# 02_VI-adc.net
KiCad netlist of a schematic drawn in Altium Designer
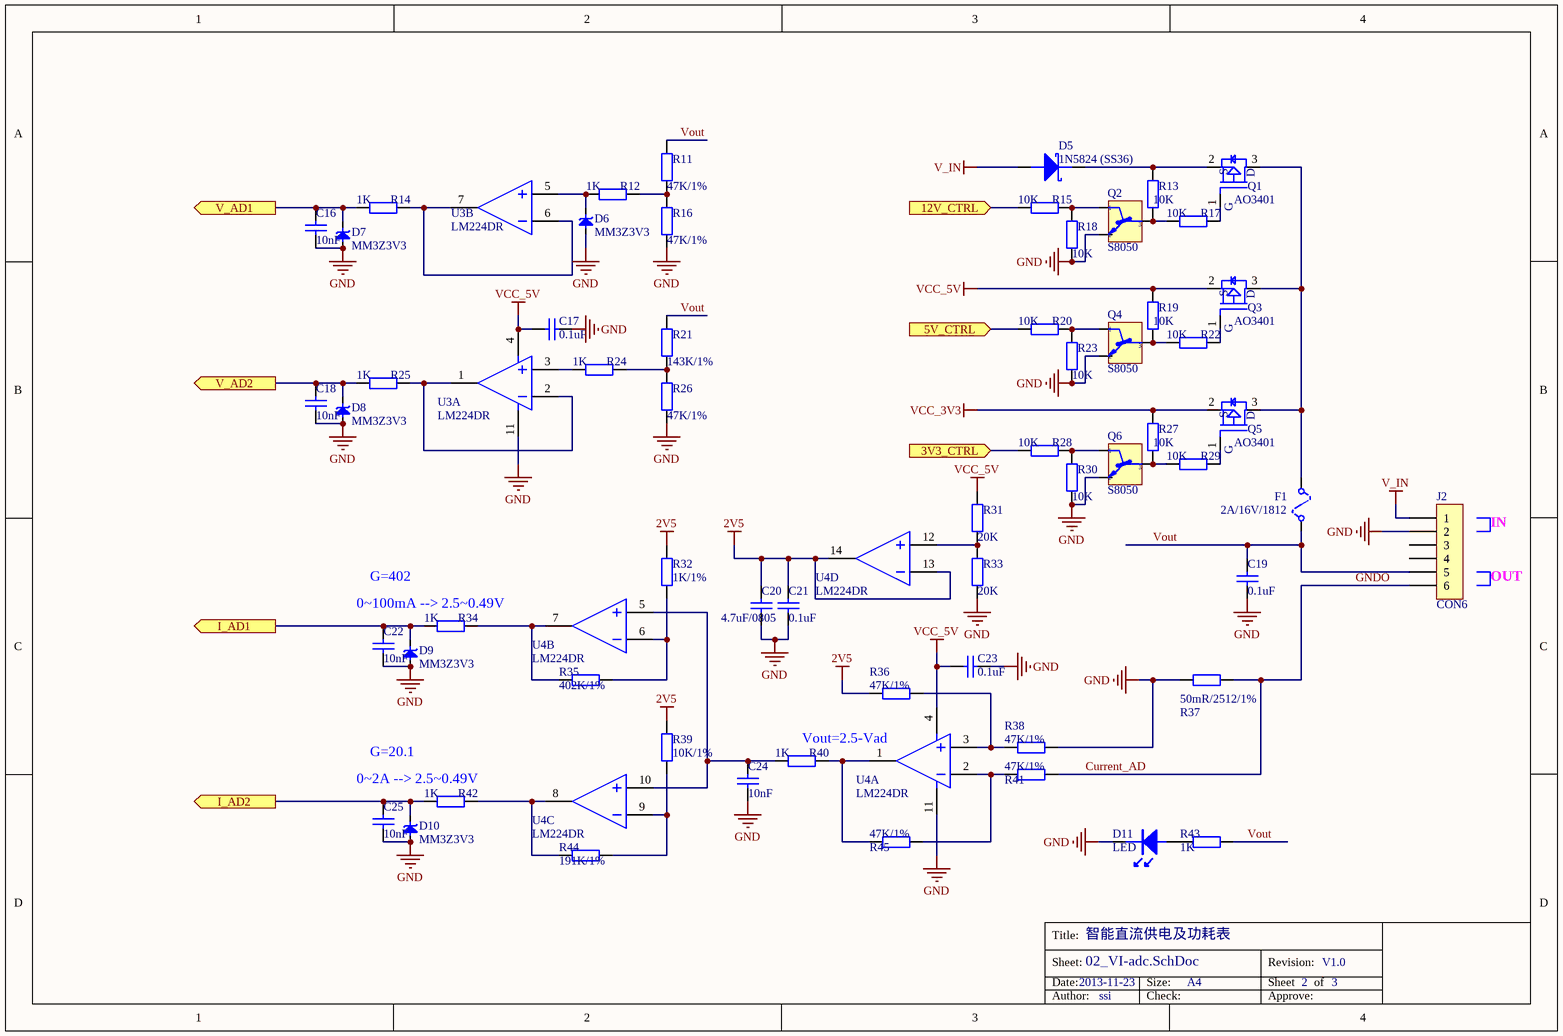
[diagram p0: 02_VI-adc.SchDoc]

(export (version "E")
  (design (tool "Eeschema 10.0.6"))
  (components
    (comp (ref "C16")
      (value "10nF")
      (footprint "0603C")
      (description "Capacitor")
      (fields (field (name "PUBLISHER") "Altium Limited"))
      (libsource (lib "SSD-Schlib1") (part "Cap"))
    )
    (comp (ref "C17")
      (value "0.1uF")
      (footprint "0603C")
      (description "Capacitor")
      (fields (field (name "PUBLISHER") "Altium Limited"))
      (libsource (lib "SSD-Schlib1") (part "Cap"))
    )
    (comp (ref "C18")
      (value "10nF")
      (footprint "0603C")
      (description "Capacitor")
      (fields (field (name "PUBLISHER") "Altium Limited"))
      (libsource (lib "SSD-Schlib1") (part "Cap"))
    )
    (comp (ref "C19")
      (value "0.1uF")
      (footprint "0603C")
      (description "Capacitor")
      (fields (field (name "PUBLISHER") "Altium Limited"))
      (libsource (lib "SSD-Schlib1") (part "Cap"))
    )
    (comp (ref "C20")
      (value "4.7uF/0805")
      (footprint "0805")
      (description "Capacitor")
      (fields (field (name "PUBLISHER") "Altium Limited"))
      (libsource (lib "SSD-Schlib1") (part "Cap"))
    )
    (comp (ref "C21")
      (value "0.1uF")
      (footprint "0603C")
      (description "Capacitor")
      (fields (field (name "PUBLISHER") "Altium Limited"))
      (libsource (lib "SSD-Schlib1") (part "Cap"))
    )
    (comp (ref "C22")
      (value "10nF")
      (footprint "0603C")
      (description "Capacitor")
      (fields (field (name "PUBLISHER") "Altium Limited"))
      (libsource (lib "SSD-Schlib1") (part "Cap"))
    )
    (comp (ref "C23")
      (value "0.1uF")
      (footprint "0603C")
      (description "Capacitor")
      (fields (field (name "PUBLISHER") "Altium Limited"))
      (libsource (lib "SSD-Schlib1") (part "Cap"))
    )
    (comp (ref "C24")
      (value "10nF")
      (footprint "0603C")
      (description "Capacitor")
      (fields (field (name "PUBLISHER") "Altium Limited"))
      (libsource (lib "SSD-Schlib1") (part "Cap"))
    )
    (comp (ref "C25")
      (value "10nF")
      (footprint "0603C")
      (description "Capacitor")
      (fields (field (name "PUBLISHER") "Altium Limited"))
      (libsource (lib "SSD-Schlib1") (part "Cap"))
    )
    (comp (ref "D5")
      (value "1N5824 (SS36)")
      (footprint "SMA/DO-214AC")
      (description "Schottky Diode")
      (libsource (lib "SSD-Schlib1") (part "DIODE_1N582x"))
    )
    (comp (ref "D6")
      (value "MM3Z3V3")
      (footprint "SOD-323")
      (description "Zener Diode")
      (fields (field (name "PUBLISHER") "Altium Limited"))
      (libsource (lib "SSD-Schlib1") (part "DIODE_MM3Zxx"))
    )
    (comp (ref "D7")
      (value "MM3Z3V3")
      (footprint "SOD-323")
      (description "Zener Diode")
      (fields (field (name "PUBLISHER") "Altium Limited"))
      (libsource (lib "SSD-Schlib1") (part "DIODE_MM3Zxx"))
    )
    (comp (ref "D8")
      (value "MM3Z3V3")
      (footprint "SOD-323")
      (description "Zener Diode")
      (fields (field (name "PUBLISHER") "Altium Limited"))
      (libsource (lib "SSD-Schlib1") (part "DIODE_MM3Zxx"))
    )
    (comp (ref "D9")
      (value "MM3Z3V3")
      (footprint "SOD-323")
      (description "Zener Diode")
      (fields (field (name "PUBLISHER") "Altium Limited"))
      (libsource (lib "SSD-Schlib1") (part "DIODE_MM3Zxx"))
    )
    (comp (ref "D10")
      (value "MM3Z3V3")
      (footprint "SOD-323")
      (description "Zener Diode")
      (fields (field (name "PUBLISHER") "Altium Limited"))
      (libsource (lib "SSD-Schlib1") (part "DIODE_MM3Zxx"))
    )
    (comp (ref "D11") (value "LED") (footprint "LED-3.5mm") (libsource (lib "SSD-Schlib1") (part "LED")))
    (comp (ref "F1")
      (value "2A/16V/1812")
      (footprint "F1812")
      (description "Fuse")
      (fields (field (name "PUBLISHER") "Altium Limited"))
      (libsource (lib "SSD-Schlib1") (part "Fuse 3"))
    )
    (comp (ref "J2") (value "CON6") (footprint "SIPD6") (libsource (lib "SSD_LibPkg") (part "CON6")))
    (comp (ref "Q1")
      (value "AO3401")
      (footprint "SOT-23")
      (libsource (lib "SSD-Schlib1") (part "MOS_P_SI2305DS"))
    )
    (comp (ref "Q2")
      (value "S8050")
      (footprint "SSD-PCBLIB1:SOT-23")
      (description "NPN")
      (libsource (lib "SSD-Schlib1") (part "NPN_T"))
    )
    (comp (ref "Q3")
      (value "AO3401")
      (footprint "SOT-23")
      (libsource (lib "SSD-Schlib1") (part "MOS_P_SI2305DS"))
    )
    (comp (ref "Q4")
      (value "S8050")
      (footprint "SSD-PCBLIB1:SOT-23")
      (description "NPN")
      (libsource (lib "SSD-Schlib1") (part "NPN_T"))
    )
    (comp (ref "Q5")
      (value "AO3401")
      (footprint "SOT-23")
      (libsource (lib "SSD-Schlib1") (part "MOS_P_SI2305DS"))
    )
    (comp (ref "Q6")
      (value "S8050")
      (footprint "SSD-PCBLIB1:SOT-23")
      (description "NPN")
      (libsource (lib "SSD-Schlib1") (part "NPN_T"))
    )
    (comp (ref "R11")
      (value "47K/1%")
      (footprint "0603")
      (description "Resistor")
      (fields (field (name "PUBLISHER") "Altium Limited"))
      (libsource (lib "SSD-Schlib1") (part "Res2"))
    )
    (comp (ref "R12")
      (value "1K")
      (footprint "0603")
      (description "Resistor")
      (fields (field (name "PUBLISHER") "Altium Limited"))
      (libsource (lib "") (part "Res2_1"))
    )
    (comp (ref "R13")
      (value "10K")
      (footprint "0603")
      (description "Resistor")
      (fields (field (name "PUBLISHER") "Altium Limited"))
      (libsource (lib "SSD-Schlib1") (part "Res2"))
    )
    (comp (ref "R14")
      (value "1K")
      (footprint "0603")
      (description "Resistor")
      (fields (field (name "PUBLISHER") "Altium Limited"))
      (libsource (lib "") (part "Res2_1"))
    )
    (comp (ref "R15")
      (value "10K")
      (footprint "0603")
      (description "Resistor")
      (fields (field (name "PUBLISHER") "Altium Limited"))
      (libsource (lib "") (part "Res2_1"))
    )
    (comp (ref "R16")
      (value "47K/1%")
      (footprint "0603")
      (description "Resistor")
      (fields (field (name "PUBLISHER") "Altium Limited"))
      (libsource (lib "SSD-Schlib1") (part "Res2"))
    )
    (comp (ref "R17")
      (value "10K")
      (footprint "0603")
      (description "Resistor")
      (fields (field (name "PUBLISHER") "Altium Limited"))
      (libsource (lib "") (part "Res2_1"))
    )
    (comp (ref "R18")
      (value "10K")
      (footprint "0603")
      (description "Resistor")
      (fields (field (name "PUBLISHER") "Altium Limited"))
      (libsource (lib "SSD-Schlib1") (part "Res2"))
    )
    (comp (ref "R19")
      (value "10K")
      (footprint "0603")
      (description "Resistor")
      (fields (field (name "PUBLISHER") "Altium Limited"))
      (libsource (lib "SSD-Schlib1") (part "Res2"))
    )
    (comp (ref "R20")
      (value "10K")
      (footprint "0603")
      (description "Resistor")
      (fields (field (name "PUBLISHER") "Altium Limited"))
      (libsource (lib "") (part "Res2_1"))
    )
    (comp (ref "R21")
      (value "143K/1%")
      (footprint "0603")
      (description "Resistor")
      (fields (field (name "PUBLISHER") "Altium Limited"))
      (libsource (lib "SSD-Schlib1") (part "Res2"))
    )
    (comp (ref "R22")
      (value "10K")
      (footprint "0603")
      (description "Resistor")
      (fields (field (name "PUBLISHER") "Altium Limited"))
      (libsource (lib "") (part "Res2_1"))
    )
    (comp (ref "R23")
      (value "10K")
      (footprint "0603")
      (description "Resistor")
      (fields (field (name "PUBLISHER") "Altium Limited"))
      (libsource (lib "SSD-Schlib1") (part "Res2"))
    )
    (comp (ref "R24")
      (value "1K")
      (footprint "0603")
      (description "Resistor")
      (fields (field (name "PUBLISHER") "Altium Limited"))
      (libsource (lib "") (part "Res2_1"))
    )
    (comp (ref "R25")
      (value "1K")
      (footprint "0603")
      (description "Resistor")
      (fields (field (name "PUBLISHER") "Altium Limited"))
      (libsource (lib "") (part "Res2_1"))
    )
    (comp (ref "R26")
      (value "47K/1%")
      (footprint "0603")
      (description "Resistor")
      (fields (field (name "PUBLISHER") "Altium Limited"))
      (libsource (lib "SSD-Schlib1") (part "Res2"))
    )
    (comp (ref "R27")
      (value "10K")
      (footprint "0603")
      (description "Resistor")
      (fields (field (name "PUBLISHER") "Altium Limited"))
      (libsource (lib "SSD-Schlib1") (part "Res2"))
    )
    (comp (ref "R28")
      (value "10K")
      (footprint "0603")
      (description "Resistor")
      (fields (field (name "PUBLISHER") "Altium Limited"))
      (libsource (lib "") (part "Res2_1"))
    )
    (comp (ref "R29")
      (value "10K")
      (footprint "0603")
      (description "Resistor")
      (fields (field (name "PUBLISHER") "Altium Limited"))
      (libsource (lib "") (part "Res2_1"))
    )
    (comp (ref "R30")
      (value "10K")
      (footprint "0603")
      (description "Resistor")
      (fields (field (name "PUBLISHER") "Altium Limited"))
      (libsource (lib "SSD-Schlib1") (part "Res2"))
    )
    (comp (ref "R31")
      (value "20K")
      (footprint "0603")
      (description "Resistor")
      (fields (field (name "PUBLISHER") "Altium Limited"))
      (libsource (lib "SSD-Schlib1") (part "Res2"))
    )
    (comp (ref "R32")
      (value "1K/1%")
      (footprint "0603")
      (description "Resistor")
      (fields (field (name "PUBLISHER") "Altium Limited"))
      (libsource (lib "") (part "Res2_2"))
    )
    (comp (ref "R33")
      (value "20K")
      (footprint "0603")
      (description "Resistor")
      (fields (field (name "PUBLISHER") "Altium Limited"))
      (libsource (lib "SSD-Schlib1") (part "Res2"))
    )
    (comp (ref "R34")
      (value "1K")
      (footprint "0603")
      (description "Resistor")
      (fields (field (name "PUBLISHER") "Altium Limited"))
      (libsource (lib "") (part "Res2_1"))
    )
    (comp (ref "R35")
      (value "402K/1%")
      (footprint "0603")
      (description "Resistor")
      (fields (field (name "PUBLISHER") "Altium Limited"))
      (libsource (lib "") (part "Res2_1"))
    )
    (comp (ref "R36")
      (value "47K/1%")
      (footprint "0603")
      (description "Resistor")
      (fields (field (name "PUBLISHER") "Altium Limited"))
      (libsource (lib "") (part "Res2_1"))
    )
    (comp (ref "R37")
      (value "50mR/2512/1%")
      (footprint "2512")
      (description "Resistor")
      (fields (field (name "PUBLISHER") "Altium Limited"))
      (libsource (lib "") (part "Res2_1"))
    )
    (comp (ref "R38")
      (value "47K/1%")
      (footprint "0603")
      (description "Resistor")
      (fields (field (name "PUBLISHER") "Altium Limited"))
      (libsource (lib "") (part "Res2_1"))
    )
    (comp (ref "R39")
      (value "10K/1%")
      (footprint "0603")
      (description "Resistor")
      (fields (field (name "PUBLISHER") "Altium Limited"))
      (libsource (lib "") (part "Res2_2"))
    )
    (comp (ref "R40")
      (value "1K")
      (footprint "0603")
      (description "Resistor")
      (fields (field (name "PUBLISHER") "Altium Limited"))
      (libsource (lib "") (part "Res2_1"))
    )
    (comp (ref "R41")
      (value "47K/1%")
      (footprint "0603")
      (description "Resistor")
      (fields (field (name "PUBLISHER") "Altium Limited"))
      (libsource (lib "") (part "Res2_1"))
    )
    (comp (ref "R42")
      (value "1K")
      (footprint "0603")
      (description "Resistor")
      (fields (field (name "PUBLISHER") "Altium Limited"))
      (libsource (lib "") (part "Res2_1"))
    )
    (comp (ref "R43")
      (value "1K")
      (footprint "0603")
      (description "Resistor")
      (fields (field (name "PUBLISHER") "Altium Limited"))
      (libsource (lib "") (part "Res2_1"))
    )
    (comp (ref "R44")
      (value "191K/1%")
      (footprint "0603")
      (description "Resistor")
      (fields (field (name "PUBLISHER") "Altium Limited"))
      (libsource (lib "") (part "Res2_1"))
    )
    (comp (ref "R45")
      (value "47K/1%")
      (footprint "0603")
      (description "Resistor")
      (fields (field (name "PUBLISHER") "Altium Limited"))
      (libsource (lib "") (part "Res2_1"))
    )
    (comp (ref "U3") (value "LM224DR") (footprint "SO-14") (libsource (lib "SSD-Schlib1") (part "LM224")))
    (comp (ref "U4") (value "LM224DR") (footprint "SO-14") (libsource (lib "SSD-Schlib1") (part "LM224")))
  )
  (nets
    (net (code "1") (name "/3V3_CTRL") (class "Default")
      (node (ref "R28") (pin "1") (pinfunction "1_1") (pintype "passive"))
    )
    (net (code "2") (name "/5V_CTRL") (class "Default")
      (node (ref "R20") (pin "1") (pinfunction "1_1") (pintype "passive"))
    )
    (net (code "3") (name "/12V_CTRL") (class "Default")
      (node (ref "R15") (pin "1") (pinfunction "1_1") (pintype "passive"))
    )
    (net (code "4") (name "/Current_AD") (class "Default")
      (node (ref "J2") (pin "6") (pinfunction "6_6") (pintype "passive"))
      (node (ref "R37") (pin "2") (pinfunction "2_2") (pintype "passive"))
      (node (ref "R41") (pin "2") (pinfunction "2_2") (pintype "passive"))
    )
    (net (code "5") (name "/I_AD1") (class "Default")
      (node (ref "C22") (pin "2") (pinfunction "2_2") (pintype "passive"))
      (node (ref "D9") (pin "2") (pinfunction "K_2") (pintype "passive"))
      (node (ref "R34") (pin "1") (pinfunction "1_1") (pintype "passive"))
    )
    (net (code "6") (name "/I_AD2") (class "Default")
      (node (ref "C25") (pin "2") (pinfunction "2_2") (pintype "passive"))
      (node (ref "D10") (pin "2") (pinfunction "K_2") (pintype "passive"))
      (node (ref "R42") (pin "1") (pinfunction "1_1") (pintype "passive"))
    )
    (net (code "7") (name "/V_AD1") (class "Default")
      (node (ref "C16") (pin "2") (pinfunction "2_2") (pintype "passive"))
      (node (ref "D7") (pin "2") (pinfunction "K_2") (pintype "passive"))
      (node (ref "R14") (pin "1") (pinfunction "1_1") (pintype "passive"))
    )
    (net (code "8") (name "/V_AD2") (class "Default")
      (node (ref "C18") (pin "2") (pinfunction "2_2") (pintype "passive"))
      (node (ref "D8") (pin "2") (pinfunction "K_2") (pintype "passive"))
      (node (ref "R25") (pin "1") (pinfunction "1_1") (pintype "passive"))
    )
    (net (code "9") (name "/Vout") (class "Default")
      (node (ref "C19") (pin "2") (pinfunction "2_2") (pintype "passive"))
      (node (ref "F1") (pin "1") (pinfunction "1_1") (pintype "passive"))
      (node (ref "J2") (pin "5") (pinfunction "5_5") (pintype "passive"))
      (node (ref "R11") (pin "2") (pinfunction "2_2") (pintype "passive"))
      (node (ref "R21") (pin "2") (pinfunction "2_2") (pintype "passive"))
      (node (ref "R43") (pin "2") (pinfunction "2_2") (pintype "passive"))
    )
    (net (code "10") (name "2V5") (class "Default")
      (node (ref "C20") (pin "2") (pinfunction "2_2") (pintype "passive"))
      (node (ref "C21") (pin "2") (pinfunction "2_2") (pintype "passive"))
      (node (ref "R32") (pin "1") (pinfunction "1_1") (pintype "passive"))
      (node (ref "R36") (pin "1") (pinfunction "1_1") (pintype "passive"))
      (node (ref "R39") (pin "1") (pinfunction "1_1") (pintype "passive"))
      (node (ref "U4") (pin "13") (pintype "passive"))
      (node (ref "U4") (pin "14") (pintype "passive"))
    )
    (net (code "11") (name "GND") (class "Default")
      (node (ref "C16") (pin "1") (pinfunction "1_1") (pintype "passive"))
      (node (ref "C17") (pin "2") (pinfunction "2_2") (pintype "passive"))
      (node (ref "C18") (pin "1") (pinfunction "1_1") (pintype "passive"))
      (node (ref "C19") (pin "1") (pinfunction "1_1") (pintype "passive"))
      (node (ref "C20") (pin "1") (pinfunction "1_1") (pintype "passive"))
      (node (ref "C21") (pin "1") (pinfunction "1_1") (pintype "passive"))
      (node (ref "C22") (pin "1") (pinfunction "1_1") (pintype "passive"))
      (node (ref "C23") (pin "2") (pinfunction "2_2") (pintype "passive"))
      (node (ref "C24") (pin "1") (pinfunction "1_1") (pintype "passive"))
      (node (ref "C25") (pin "1") (pinfunction "1_1") (pintype "passive"))
      (node (ref "D10") (pin "1") (pinfunction "A_1") (pintype "passive"))
      (node (ref "D11") (pin "2") (pinfunction "K_2") (pintype "passive"))
      (node (ref "D6") (pin "1") (pinfunction "A_1") (pintype "passive"))
      (node (ref "D7") (pin "1") (pinfunction "A_1") (pintype "passive"))
      (node (ref "D8") (pin "1") (pinfunction "A_1") (pintype "passive"))
      (node (ref "D9") (pin "1") (pinfunction "A_1") (pintype "passive"))
      (node (ref "J2") (pin "2") (pinfunction "2_2") (pintype "passive"))
      (node (ref "Q2") (pin "2") (pinfunction "E_2") (pintype "passive"))
      (node (ref "Q4") (pin "2") (pinfunction "E_2") (pintype "passive"))
      (node (ref "Q6") (pin "2") (pinfunction "E_2") (pintype "passive"))
      (node (ref "R16") (pin "1") (pinfunction "1_1") (pintype "passive"))
      (node (ref "R18") (pin "1") (pinfunction "1_1") (pintype "passive"))
      (node (ref "R23") (pin "1") (pinfunction "1_1") (pintype "passive"))
      (node (ref "R26") (pin "1") (pinfunction "1_1") (pintype "passive"))
      (node (ref "R30") (pin "1") (pinfunction "1_1") (pintype "passive"))
      (node (ref "R33") (pin "1") (pinfunction "1_1") (pintype "passive"))
      (node (ref "R37") (pin "1") (pinfunction "1_1") (pintype "passive"))
      (node (ref "R38") (pin "2") (pinfunction "2_2") (pintype "passive"))
      (node (ref "U3") (pin "11") (pintype "passive"))
      (node (ref "U4") (pin "11") (pintype "passive"))
    )
    (net (code "12") (name "Net-(C24-Pad2)") (class "Default")
      (node (ref "C24") (pin "2") (pinfunction "2_2") (pintype "passive"))
      (node (ref "R40") (pin "1") (pinfunction "1_1") (pintype "passive"))
      (node (ref "U4") (pin "10") (pintype "passive"))
      (node (ref "U4") (pin "5") (pintype "passive"))
    )
    (net (code "13") (name "Net-(D5-K)") (class "Default")
      (node (ref "D5") (pin "2") (pinfunction "K_2") (pintype "passive"))
      (node (ref "Q1") (pin "2") (pinfunction "S_2") (pintype "passive"))
      (node (ref "R13") (pin "2") (pinfunction "2_2") (pintype "passive"))
    )
    (net (code "14") (name "Net-(D6-K)") (class "Default")
      (node (ref "D6") (pin "2") (pinfunction "K_2") (pintype "passive"))
      (node (ref "R12") (pin "1") (pinfunction "1_1") (pintype "passive"))
      (node (ref "U3") (pin "5") (pintype "passive"))
    )
    (net (code "15") (name "Net-(D11-A)") (class "Default")
      (node (ref "D11") (pin "1") (pinfunction "A_1") (pintype "passive"))
      (node (ref "R43") (pin "1") (pinfunction "1_1") (pintype "passive"))
    )
    (net (code "16") (name "Net-(Q1-D)") (class "Default")
      (node (ref "F1") (pin "2") (pinfunction "2_2") (pintype "passive"))
      (node (ref "Q1") (pin "3") (pinfunction "D_3") (pintype "passive"))
      (node (ref "Q3") (pin "3") (pinfunction "D_3") (pintype "passive"))
      (node (ref "Q5") (pin "3") (pinfunction "D_3") (pintype "passive"))
    )
    (net (code "17") (name "Net-(Q1-G)") (class "Default")
      (node (ref "Q1") (pin "1") (pinfunction "G_1") (pintype "passive"))
      (node (ref "R17") (pin "2") (pinfunction "2_2") (pintype "passive"))
    )
    (net (code "18") (name "Net-(Q2-B)") (class "Default")
      (node (ref "Q2") (pin "1") (pinfunction "B_1") (pintype "passive"))
      (node (ref "R15") (pin "2") (pinfunction "2_2") (pintype "passive"))
      (node (ref "R18") (pin "2") (pinfunction "2_2") (pintype "passive"))
    )
    (net (code "19") (name "Net-(Q2-C)") (class "Default")
      (node (ref "Q2") (pin "3") (pinfunction "C_3") (pintype "passive"))
      (node (ref "R13") (pin "1") (pinfunction "1_1") (pintype "passive"))
      (node (ref "R17") (pin "1") (pinfunction "1_1") (pintype "passive"))
    )
    (net (code "20") (name "Net-(Q3-G)") (class "Default")
      (node (ref "Q3") (pin "1") (pinfunction "G_1") (pintype "passive"))
      (node (ref "R22") (pin "2") (pinfunction "2_2") (pintype "passive"))
    )
    (net (code "21") (name "Net-(Q4-B)") (class "Default")
      (node (ref "Q4") (pin "1") (pinfunction "B_1") (pintype "passive"))
      (node (ref "R20") (pin "2") (pinfunction "2_2") (pintype "passive"))
      (node (ref "R23") (pin "2") (pinfunction "2_2") (pintype "passive"))
    )
    (net (code "22") (name "Net-(Q4-C)") (class "Default")
      (node (ref "Q4") (pin "3") (pinfunction "C_3") (pintype "passive"))
      (node (ref "R19") (pin "1") (pinfunction "1_1") (pintype "passive"))
      (node (ref "R22") (pin "1") (pinfunction "1_1") (pintype "passive"))
    )
    (net (code "23") (name "Net-(Q5-G)") (class "Default")
      (node (ref "Q5") (pin "1") (pinfunction "G_1") (pintype "passive"))
      (node (ref "R29") (pin "2") (pinfunction "2_2") (pintype "passive"))
    )
    (net (code "24") (name "Net-(Q6-B)") (class "Default")
      (node (ref "Q6") (pin "1") (pinfunction "B_1") (pintype "passive"))
      (node (ref "R28") (pin "2") (pinfunction "2_2") (pintype "passive"))
      (node (ref "R30") (pin "2") (pinfunction "2_2") (pintype "passive"))
    )
    (net (code "25") (name "Net-(Q6-C)") (class "Default")
      (node (ref "Q6") (pin "3") (pinfunction "C_3") (pintype "passive"))
      (node (ref "R27") (pin "1") (pinfunction "1_1") (pintype "passive"))
      (node (ref "R29") (pin "1") (pinfunction "1_1") (pintype "passive"))
    )
    (net (code "26") (name "Net-(R11-Pad1)") (class "Default")
      (node (ref "R11") (pin "1") (pinfunction "1_1") (pintype "passive"))
      (node (ref "R12") (pin "2") (pinfunction "2_2") (pintype "passive"))
      (node (ref "R16") (pin "2") (pinfunction "2_2") (pintype "passive"))
    )
    (net (code "27") (name "Net-(R14-Pad2)") (class "Default")
      (node (ref "R14") (pin "2") (pinfunction "2_2") (pintype "passive"))
      (node (ref "U3") (pin "6") (pintype "passive"))
      (node (ref "U3") (pin "7") (pintype "passive"))
    )
    (net (code "28") (name "Net-(R21-Pad1)") (class "Default")
      (node (ref "R21") (pin "1") (pinfunction "1_1") (pintype "passive"))
      (node (ref "R24") (pin "2") (pinfunction "2_2") (pintype "passive"))
      (node (ref "R26") (pin "2") (pinfunction "2_2") (pintype "passive"))
    )
    (net (code "29") (name "Net-(R24-Pad1)") (class "Default")
      (node (ref "R24") (pin "1") (pinfunction "1_1") (pintype "passive"))
      (node (ref "U3") (pin "3") (pintype "passive"))
    )
    (net (code "30") (name "Net-(R25-Pad2)") (class "Default")
      (node (ref "R25") (pin "2") (pinfunction "2_2") (pintype "passive"))
      (node (ref "U3") (pin "1") (pintype "passive"))
      (node (ref "U3") (pin "2") (pintype "passive"))
    )
    (net (code "31") (name "Net-(R31-Pad1)") (class "Default")
      (node (ref "R31") (pin "1") (pinfunction "1_1") (pintype "passive"))
      (node (ref "R33") (pin "2") (pinfunction "2_2") (pintype "passive"))
      (node (ref "U4") (pin "12") (pintype "passive"))
    )
    (net (code "32") (name "Net-(R32-Pad2)") (class "Default")
      (node (ref "R32") (pin "2") (pinfunction "2_2") (pintype "passive"))
      (node (ref "R35") (pin "2") (pinfunction "2_2") (pintype "passive"))
      (node (ref "U4") (pin "6") (pintype "passive"))
    )
    (net (code "33") (name "Net-(R34-Pad2)") (class "Default")
      (node (ref "R34") (pin "2") (pinfunction "2_2") (pintype "passive"))
      (node (ref "R35") (pin "1") (pinfunction "1_1") (pintype "passive"))
      (node (ref "U4") (pin "7") (pintype "passive"))
    )
    (net (code "34") (name "Net-(R36-Pad2)") (class "Default")
      (node (ref "R36") (pin "2") (pinfunction "2_2") (pintype "passive"))
      (node (ref "R38") (pin "1") (pinfunction "1_1") (pintype "passive"))
      (node (ref "U4") (pin "3") (pintype "passive"))
    )
    (net (code "35") (name "Net-(R39-Pad2)") (class "Default")
      (node (ref "R39") (pin "2") (pinfunction "2_2") (pintype "passive"))
      (node (ref "R44") (pin "2") (pinfunction "2_2") (pintype "passive"))
      (node (ref "U4") (pin "9") (pintype "passive"))
    )
    (net (code "36") (name "Net-(R40-Pad2)") (class "Default")
      (node (ref "R40") (pin "2") (pinfunction "2_2") (pintype "passive"))
      (node (ref "R45") (pin "1") (pinfunction "1_1") (pintype "passive"))
      (node (ref "U4") (pin "1") (pintype "passive"))
    )
    (net (code "37") (name "Net-(R41-Pad1)") (class "Default")
      (node (ref "R41") (pin "1") (pinfunction "1_1") (pintype "passive"))
      (node (ref "R45") (pin "2") (pinfunction "2_2") (pintype "passive"))
      (node (ref "U4") (pin "2") (pintype "passive"))
    )
    (net (code "38") (name "Net-(R42-Pad2)") (class "Default")
      (node (ref "R42") (pin "2") (pinfunction "2_2") (pintype "passive"))
      (node (ref "R44") (pin "1") (pinfunction "1_1") (pintype "passive"))
      (node (ref "U4") (pin "8") (pintype "passive"))
    )
    (net (code "39") (name "VCC_3V3") (class "Default")
      (node (ref "Q5") (pin "2") (pinfunction "S_2") (pintype "passive"))
      (node (ref "R27") (pin "2") (pinfunction "2_2") (pintype "passive"))
    )
    (net (code "40") (name "VCC_5V") (class "Default")
      (node (ref "C17") (pin "1") (pinfunction "1_1") (pintype "passive"))
      (node (ref "C23") (pin "1") (pinfunction "1_1") (pintype "passive"))
      (node (ref "Q3") (pin "2") (pinfunction "S_2") (pintype "passive"))
      (node (ref "R19") (pin "2") (pinfunction "2_2") (pintype "passive"))
      (node (ref "R31") (pin "2") (pinfunction "2_2") (pintype "passive"))
      (node (ref "U3") (pin "4") (pintype "passive"))
      (node (ref "U4") (pin "4") (pintype "passive"))
    )
    (net (code "41") (name "V_IN") (class "Default")
      (node (ref "D5") (pin "1") (pinfunction "A_1") (pintype "passive"))
      (node (ref "J2") (pin "1") (pinfunction "1_1") (pintype "passive"))
    )
    (net (code "42") (name "unconnected-(J2-Pad3)") (class "Default")
      (node (ref "J2") (pin "3") (pinfunction "3_3") (pintype "passive"))
    )
    (net (code "43") (name "unconnected-(J2-Pad4)") (class "Default")
      (node (ref "J2") (pin "4") (pinfunction "4_4") (pintype "passive"))
    )
  )
)
